# ring.net
KiCad netlist of a schematic drawn in EAGLE
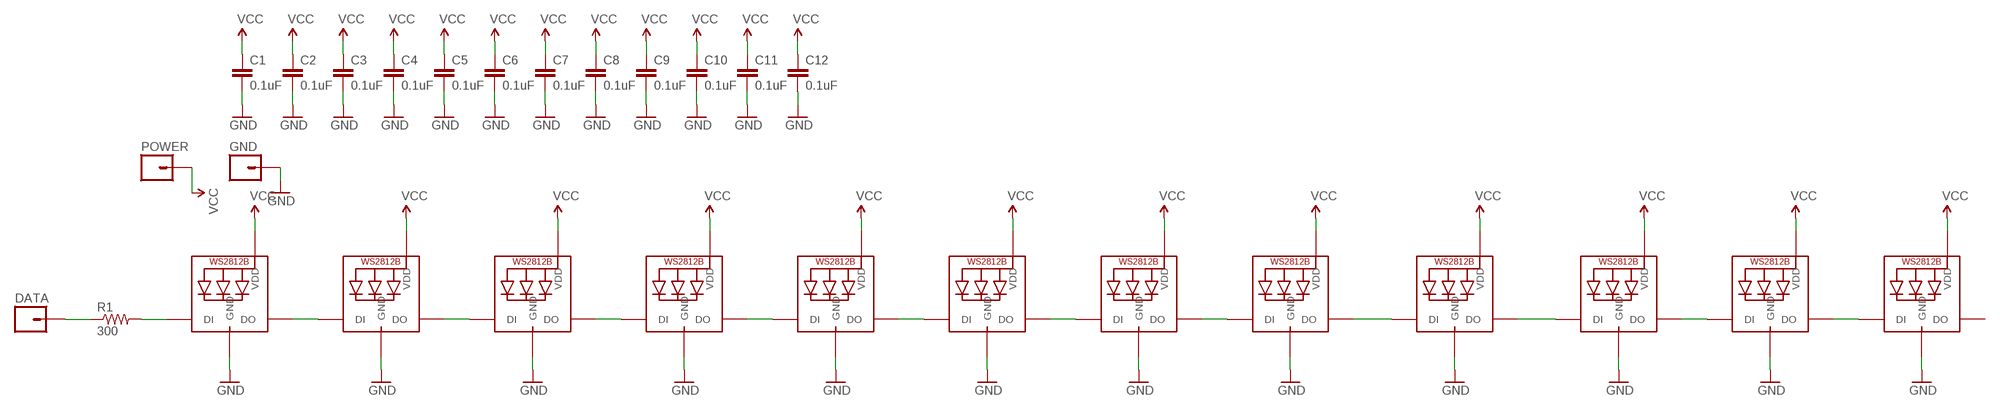
[diagram p0: schematic, sheet 1]

(export (version "E")
  (design (tool "Eeschema 10.0.6"))
  (components
    (comp (ref "C1")
      (value "0.1uF")
      (footprint "eagle-import:0603-CAP")
      (libsource (lib "eagle-import") (part "0.1UF-25V-5%(0603)"))
    )
    (comp (ref "C2")
      (value "0.1uF")
      (footprint "eagle-import:0603-CAP")
      (libsource (lib "eagle-import") (part "0.1UF-25V-5%(0603)"))
    )
    (comp (ref "C3")
      (value "0.1uF")
      (footprint "eagle-import:0603-CAP")
      (libsource (lib "eagle-import") (part "0.1UF-25V-5%(0603)"))
    )
    (comp (ref "C4")
      (value "0.1uF")
      (footprint "eagle-import:0603-CAP")
      (libsource (lib "eagle-import") (part "0.1UF-25V-5%(0603)"))
    )
    (comp (ref "C5")
      (value "0.1uF")
      (footprint "eagle-import:0603-CAP")
      (libsource (lib "eagle-import") (part "0.1UF-25V-5%(0603)"))
    )
    (comp (ref "C6")
      (value "0.1uF")
      (footprint "eagle-import:0603-CAP")
      (libsource (lib "eagle-import") (part "0.1UF-25V-5%(0603)"))
    )
    (comp (ref "C7")
      (value "0.1uF")
      (footprint "eagle-import:0603-CAP")
      (libsource (lib "eagle-import") (part "0.1UF-25V-5%(0603)"))
    )
    (comp (ref "C8")
      (value "0.1uF")
      (footprint "eagle-import:0603-CAP")
      (libsource (lib "eagle-import") (part "0.1UF-25V-5%(0603)"))
    )
    (comp (ref "C9")
      (value "0.1uF")
      (footprint "eagle-import:0603-CAP")
      (libsource (lib "eagle-import") (part "0.1UF-25V-5%(0603)"))
    )
    (comp (ref "C10")
      (value "0.1uF")
      (footprint "eagle-import:0603-CAP")
      (libsource (lib "eagle-import") (part "0.1UF-25V-5%(0603)"))
    )
    (comp (ref "C11")
      (value "0.1uF")
      (footprint "eagle-import:0603-CAP")
      (libsource (lib "eagle-import") (part "0.1UF-25V-5%(0603)"))
    )
    (comp (ref "C12")
      (value "0.1uF")
      (footprint "eagle-import:0603-CAP")
      (libsource (lib "eagle-import") (part "0.1UF-25V-5%(0603)"))
    )
    (comp (ref "DATA")
      (value "M01PTH")
      (footprint "eagle-import:1X01")
      (libsource (lib "eagle-import") (part "M01PTH"))
    )
    (comp (ref "GND")
      (value "M01PTH")
      (footprint "eagle-import:1X01")
      (libsource (lib "eagle-import") (part "M01PTH"))
    )
    (comp (ref "LED1")
      (value "WS2812B5050")
      (footprint "eagle-import:WS2812B")
      (libsource (lib "eagle-import") (part "WS2812B5050"))
    )
    (comp (ref "LED2")
      (value "WS2812B5050")
      (footprint "eagle-import:WS2812B")
      (libsource (lib "eagle-import") (part "WS2812B5050"))
    )
    (comp (ref "LED3")
      (value "WS2812B5050")
      (footprint "eagle-import:WS2812B")
      (libsource (lib "eagle-import") (part "WS2812B5050"))
    )
    (comp (ref "LED4")
      (value "WS2812B5050")
      (footprint "eagle-import:WS2812B")
      (libsource (lib "eagle-import") (part "WS2812B5050"))
    )
    (comp (ref "LED5")
      (value "WS2812B5050")
      (footprint "eagle-import:WS2812B")
      (libsource (lib "eagle-import") (part "WS2812B5050"))
    )
    (comp (ref "LED6")
      (value "WS2812B5050")
      (footprint "eagle-import:WS2812B")
      (libsource (lib "eagle-import") (part "WS2812B5050"))
    )
    (comp (ref "LED7")
      (value "WS2812B5050")
      (footprint "eagle-import:WS2812B")
      (libsource (lib "eagle-import") (part "WS2812B5050"))
    )
    (comp (ref "LED8")
      (value "WS2812B5050")
      (footprint "eagle-import:WS2812B")
      (libsource (lib "eagle-import") (part "WS2812B5050"))
    )
    (comp (ref "LED9")
      (value "WS2812B5050")
      (footprint "eagle-import:WS2812B")
      (libsource (lib "eagle-import") (part "WS2812B5050"))
    )
    (comp (ref "LED10")
      (value "WS2812B5050")
      (footprint "eagle-import:WS2812B")
      (libsource (lib "eagle-import") (part "WS2812B5050"))
    )
    (comp (ref "LED11")
      (value "WS2812B5050")
      (footprint "eagle-import:WS2812B")
      (libsource (lib "eagle-import") (part "WS2812B5050"))
    )
    (comp (ref "LED12")
      (value "WS2812B5050")
      (footprint "eagle-import:WS2812B")
      (libsource (lib "eagle-import") (part "WS2812B5050"))
    )
    (comp (ref "POWER")
      (value "M01PTH")
      (footprint "eagle-import:1X01")
      (libsource (lib "eagle-import") (part "M01PTH"))
    )
    (comp (ref "R1")
      (value "300")
      (footprint "eagle-import:0603-RES")
      (libsource (lib "eagle-import") (part "300OHM-1/10W-1%(0603)"))
    )
  )
  (nets
    (net (code "1") (name "GND") (class "Default")
      (node (ref "C1") (pin "2") (pinfunction "2_2") (pintype "passive"))
      (node (ref "C10") (pin "2") (pinfunction "2_2") (pintype "passive"))
      (node (ref "C11") (pin "2") (pinfunction "2_2") (pintype "passive"))
      (node (ref "C12") (pin "2") (pinfunction "2_2") (pintype "passive"))
      (node (ref "C2") (pin "2") (pinfunction "2_2") (pintype "passive"))
      (node (ref "C3") (pin "2") (pinfunction "2_2") (pintype "passive"))
      (node (ref "C4") (pin "2") (pinfunction "2_2") (pintype "passive"))
      (node (ref "C5") (pin "2") (pinfunction "2_2") (pintype "passive"))
      (node (ref "C6") (pin "2") (pinfunction "2_2") (pintype "passive"))
      (node (ref "C7") (pin "2") (pinfunction "2_2") (pintype "passive"))
      (node (ref "C8") (pin "2") (pinfunction "2_2") (pintype "passive"))
      (node (ref "C9") (pin "2") (pinfunction "2_2") (pintype "passive"))
      (node (ref "GND") (pin "1") (pinfunction "1_1") (pintype "passive"))
      (node (ref "LED1") (pin "3-GND") (pinfunction "GND_3-GND") (pintype "power_in"))
      (node (ref "LED10") (pin "3-GND") (pinfunction "GND_3-GND") (pintype "power_in"))
      (node (ref "LED11") (pin "3-GND") (pinfunction "GND_3-GND") (pintype "power_in"))
      (node (ref "LED12") (pin "3-GND") (pinfunction "GND_3-GND") (pintype "power_in"))
      (node (ref "LED2") (pin "3-GND") (pinfunction "GND_3-GND") (pintype "power_in"))
      (node (ref "LED3") (pin "3-GND") (pinfunction "GND_3-GND") (pintype "power_in"))
      (node (ref "LED4") (pin "3-GND") (pinfunction "GND_3-GND") (pintype "power_in"))
      (node (ref "LED5") (pin "3-GND") (pinfunction "GND_3-GND") (pintype "power_in"))
      (node (ref "LED6") (pin "3-GND") (pinfunction "GND_3-GND") (pintype "power_in"))
      (node (ref "LED7") (pin "3-GND") (pinfunction "GND_3-GND") (pintype "power_in"))
      (node (ref "LED8") (pin "3-GND") (pinfunction "GND_3-GND") (pintype "power_in"))
      (node (ref "LED9") (pin "3-GND") (pinfunction "GND_3-GND") (pintype "power_in"))
    )
    (net (code "2") (name "Net-(DATA-Pad1)") (class "Default")
      (node (ref "DATA") (pin "1") (pinfunction "1_1") (pintype "passive"))
      (node (ref "R1") (pin "1") (pinfunction "1_1") (pintype "passive"))
    )
    (net (code "3") (name "Net-(LED1-DI)") (class "Default")
      (node (ref "LED1") (pin "4-DIN") (pinfunction "DI_4-DIN") (pintype "input"))
      (node (ref "R1") (pin "2") (pinfunction "2_2") (pintype "passive"))
    )
    (net (code "4") (name "Net-(LED1-DO)") (class "Default")
      (node (ref "LED1") (pin "2-DOUT") (pinfunction "DO_2-DOUT") (pintype "output"))
      (node (ref "LED2") (pin "4-DIN") (pinfunction "DI_4-DIN") (pintype "input"))
    )
    (net (code "5") (name "Net-(LED2-DO)") (class "Default")
      (node (ref "LED2") (pin "2-DOUT") (pinfunction "DO_2-DOUT") (pintype "output"))
      (node (ref "LED3") (pin "4-DIN") (pinfunction "DI_4-DIN") (pintype "input"))
    )
    (net (code "6") (name "Net-(LED3-DO)") (class "Default")
      (node (ref "LED3") (pin "2-DOUT") (pinfunction "DO_2-DOUT") (pintype "output"))
      (node (ref "LED4") (pin "4-DIN") (pinfunction "DI_4-DIN") (pintype "input"))
    )
    (net (code "7") (name "Net-(LED4-DO)") (class "Default")
      (node (ref "LED4") (pin "2-DOUT") (pinfunction "DO_2-DOUT") (pintype "output"))
      (node (ref "LED5") (pin "4-DIN") (pinfunction "DI_4-DIN") (pintype "input"))
    )
    (net (code "8") (name "Net-(LED5-DO)") (class "Default")
      (node (ref "LED5") (pin "2-DOUT") (pinfunction "DO_2-DOUT") (pintype "output"))
      (node (ref "LED6") (pin "4-DIN") (pinfunction "DI_4-DIN") (pintype "input"))
    )
    (net (code "9") (name "Net-(LED6-DO)") (class "Default")
      (node (ref "LED6") (pin "2-DOUT") (pinfunction "DO_2-DOUT") (pintype "output"))
      (node (ref "LED7") (pin "4-DIN") (pinfunction "DI_4-DIN") (pintype "input"))
    )
    (net (code "10") (name "Net-(LED7-DO)") (class "Default")
      (node (ref "LED7") (pin "2-DOUT") (pinfunction "DO_2-DOUT") (pintype "output"))
      (node (ref "LED8") (pin "4-DIN") (pinfunction "DI_4-DIN") (pintype "input"))
    )
    (net (code "11") (name "Net-(LED8-DO)") (class "Default")
      (node (ref "LED8") (pin "2-DOUT") (pinfunction "DO_2-DOUT") (pintype "output"))
      (node (ref "LED9") (pin "4-DIN") (pinfunction "DI_4-DIN") (pintype "input"))
    )
    (net (code "12") (name "Net-(LED10-DI)") (class "Default")
      (node (ref "LED10") (pin "4-DIN") (pinfunction "DI_4-DIN") (pintype "input"))
      (node (ref "LED9") (pin "2-DOUT") (pinfunction "DO_2-DOUT") (pintype "output"))
    )
    (net (code "13") (name "Net-(LED10-DO)") (class "Default")
      (node (ref "LED10") (pin "2-DOUT") (pinfunction "DO_2-DOUT") (pintype "output"))
      (node (ref "LED11") (pin "4-DIN") (pinfunction "DI_4-DIN") (pintype "input"))
    )
    (net (code "14") (name "Net-(LED11-DO)") (class "Default")
      (node (ref "LED11") (pin "2-DOUT") (pinfunction "DO_2-DOUT") (pintype "output"))
      (node (ref "LED12") (pin "4-DIN") (pinfunction "DI_4-DIN") (pintype "input"))
    )
    (net (code "15") (name "VCC") (class "Default")
      (node (ref "C1") (pin "1") (pinfunction "1_1") (pintype "passive"))
      (node (ref "C10") (pin "1") (pinfunction "1_1") (pintype "passive"))
      (node (ref "C11") (pin "1") (pinfunction "1_1") (pintype "passive"))
      (node (ref "C12") (pin "1") (pinfunction "1_1") (pintype "passive"))
      (node (ref "C2") (pin "1") (pinfunction "1_1") (pintype "passive"))
      (node (ref "C3") (pin "1") (pinfunction "1_1") (pintype "passive"))
      (node (ref "C4") (pin "1") (pinfunction "1_1") (pintype "passive"))
      (node (ref "C5") (pin "1") (pinfunction "1_1") (pintype "passive"))
      (node (ref "C6") (pin "1") (pinfunction "1_1") (pintype "passive"))
      (node (ref "C7") (pin "1") (pinfunction "1_1") (pintype "passive"))
      (node (ref "C8") (pin "1") (pinfunction "1_1") (pintype "passive"))
      (node (ref "C9") (pin "1") (pinfunction "1_1") (pintype "passive"))
      (node (ref "LED1") (pin "1-VDD") (pinfunction "VDD_1-VDD") (pintype "power_in"))
      (node (ref "LED10") (pin "1-VDD") (pinfunction "VDD_1-VDD") (pintype "power_in"))
      (node (ref "LED11") (pin "1-VDD") (pinfunction "VDD_1-VDD") (pintype "power_in"))
      (node (ref "LED12") (pin "1-VDD") (pinfunction "VDD_1-VDD") (pintype "power_in"))
      (node (ref "LED2") (pin "1-VDD") (pinfunction "VDD_1-VDD") (pintype "power_in"))
      (node (ref "LED3") (pin "1-VDD") (pinfunction "VDD_1-VDD") (pintype "power_in"))
      (node (ref "LED4") (pin "1-VDD") (pinfunction "VDD_1-VDD") (pintype "power_in"))
      (node (ref "LED5") (pin "1-VDD") (pinfunction "VDD_1-VDD") (pintype "power_in"))
      (node (ref "LED6") (pin "1-VDD") (pinfunction "VDD_1-VDD") (pintype "power_in"))
      (node (ref "LED7") (pin "1-VDD") (pinfunction "VDD_1-VDD") (pintype "power_in"))
      (node (ref "LED8") (pin "1-VDD") (pinfunction "VDD_1-VDD") (pintype "power_in"))
      (node (ref "LED9") (pin "1-VDD") (pinfunction "VDD_1-VDD") (pintype "power_in"))
      (node (ref "POWER") (pin "1") (pinfunction "1_1") (pintype "passive"))
    )
    (net (code "16") (name "unconnected-(LED12-DO-Pad2-DOUT)") (class "Default")
      (node (ref "LED12") (pin "2-DOUT") (pinfunction "DO_2-DOUT") (pintype "output"))
    )
  )
)
